# TurretController.net
KiCad netlist of a schematic drawn in EAGLE
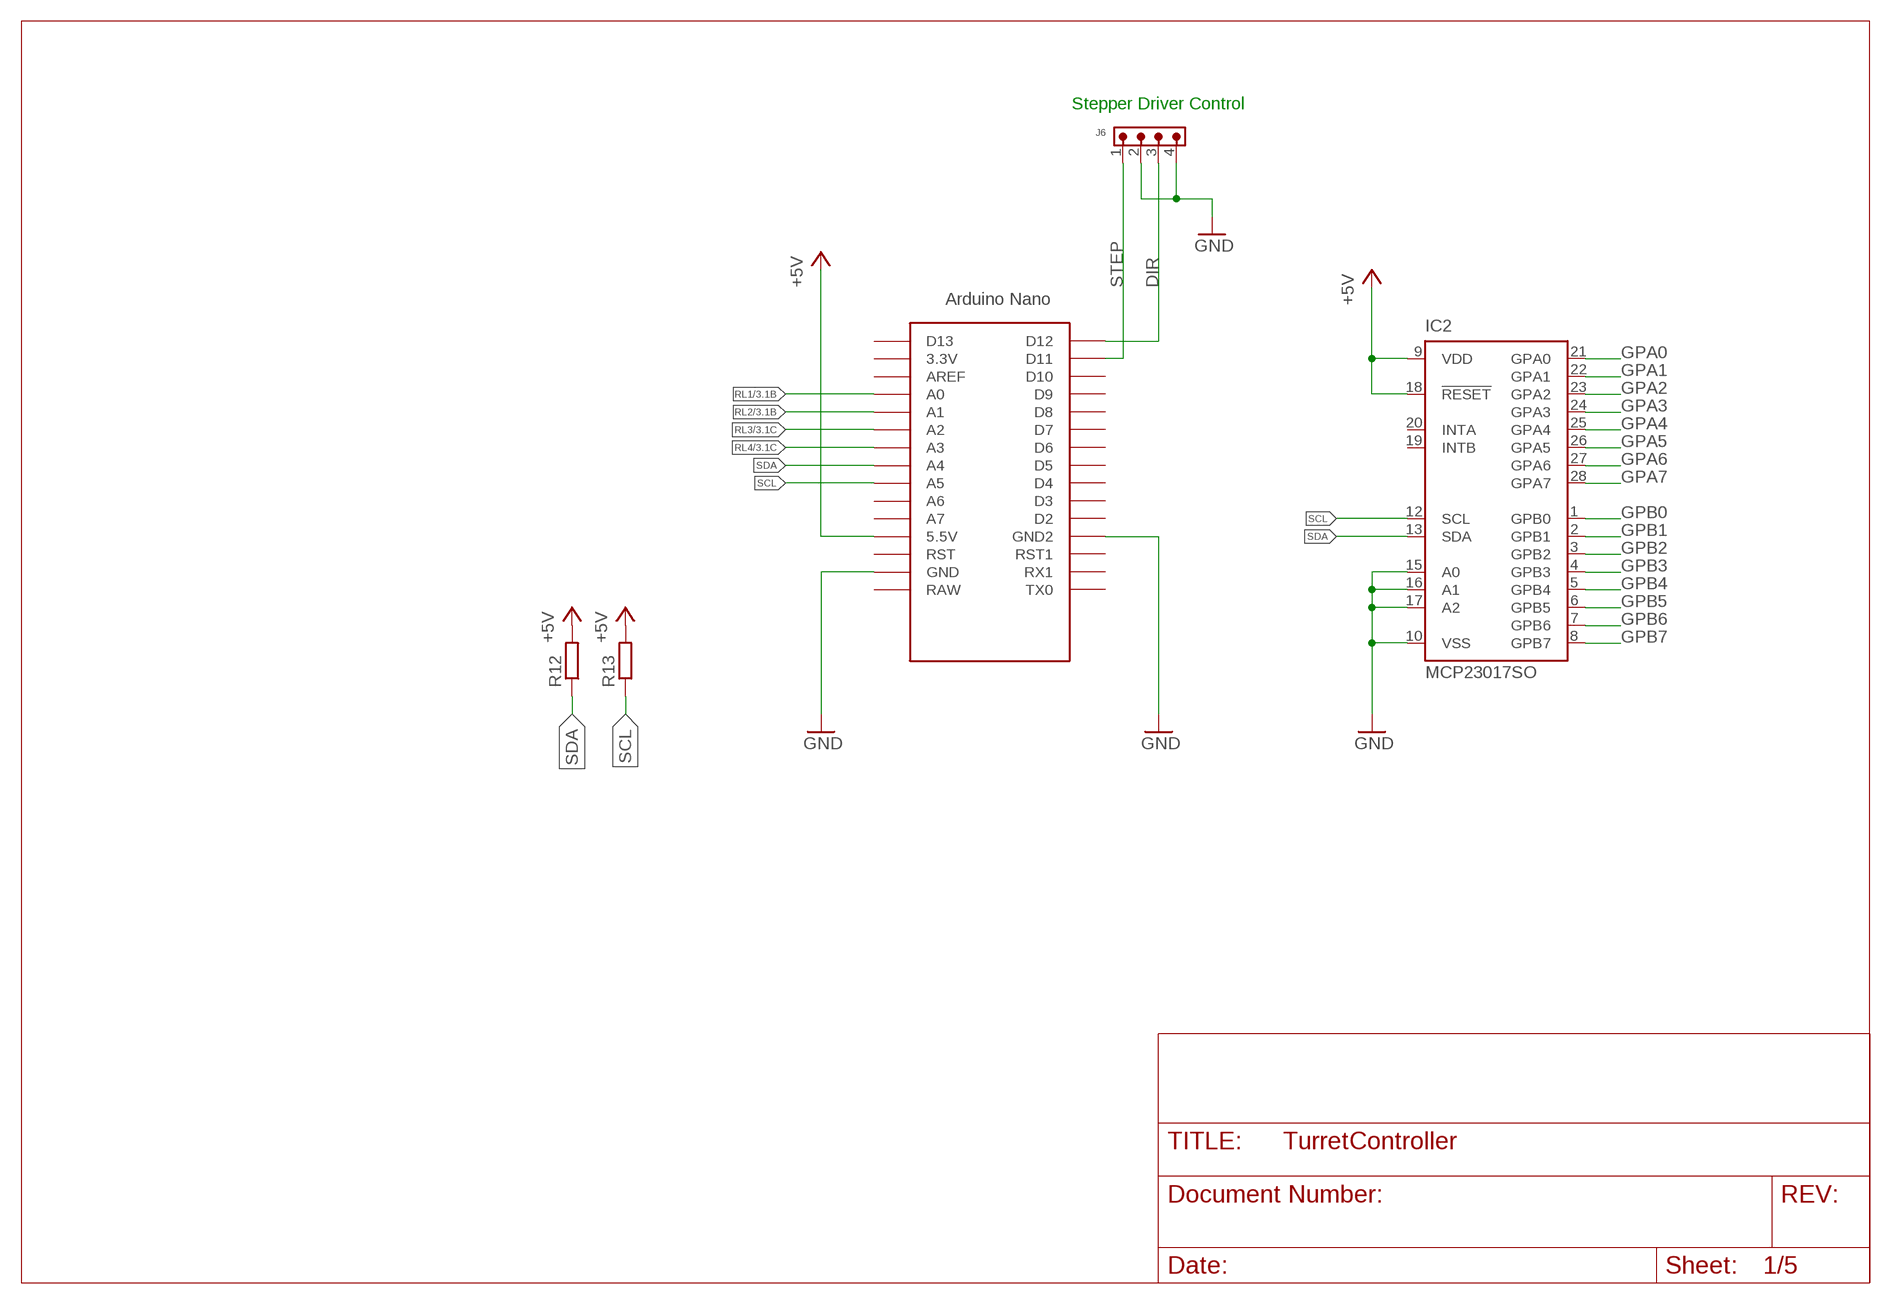
[diagram p0: schematic, sheet 1]
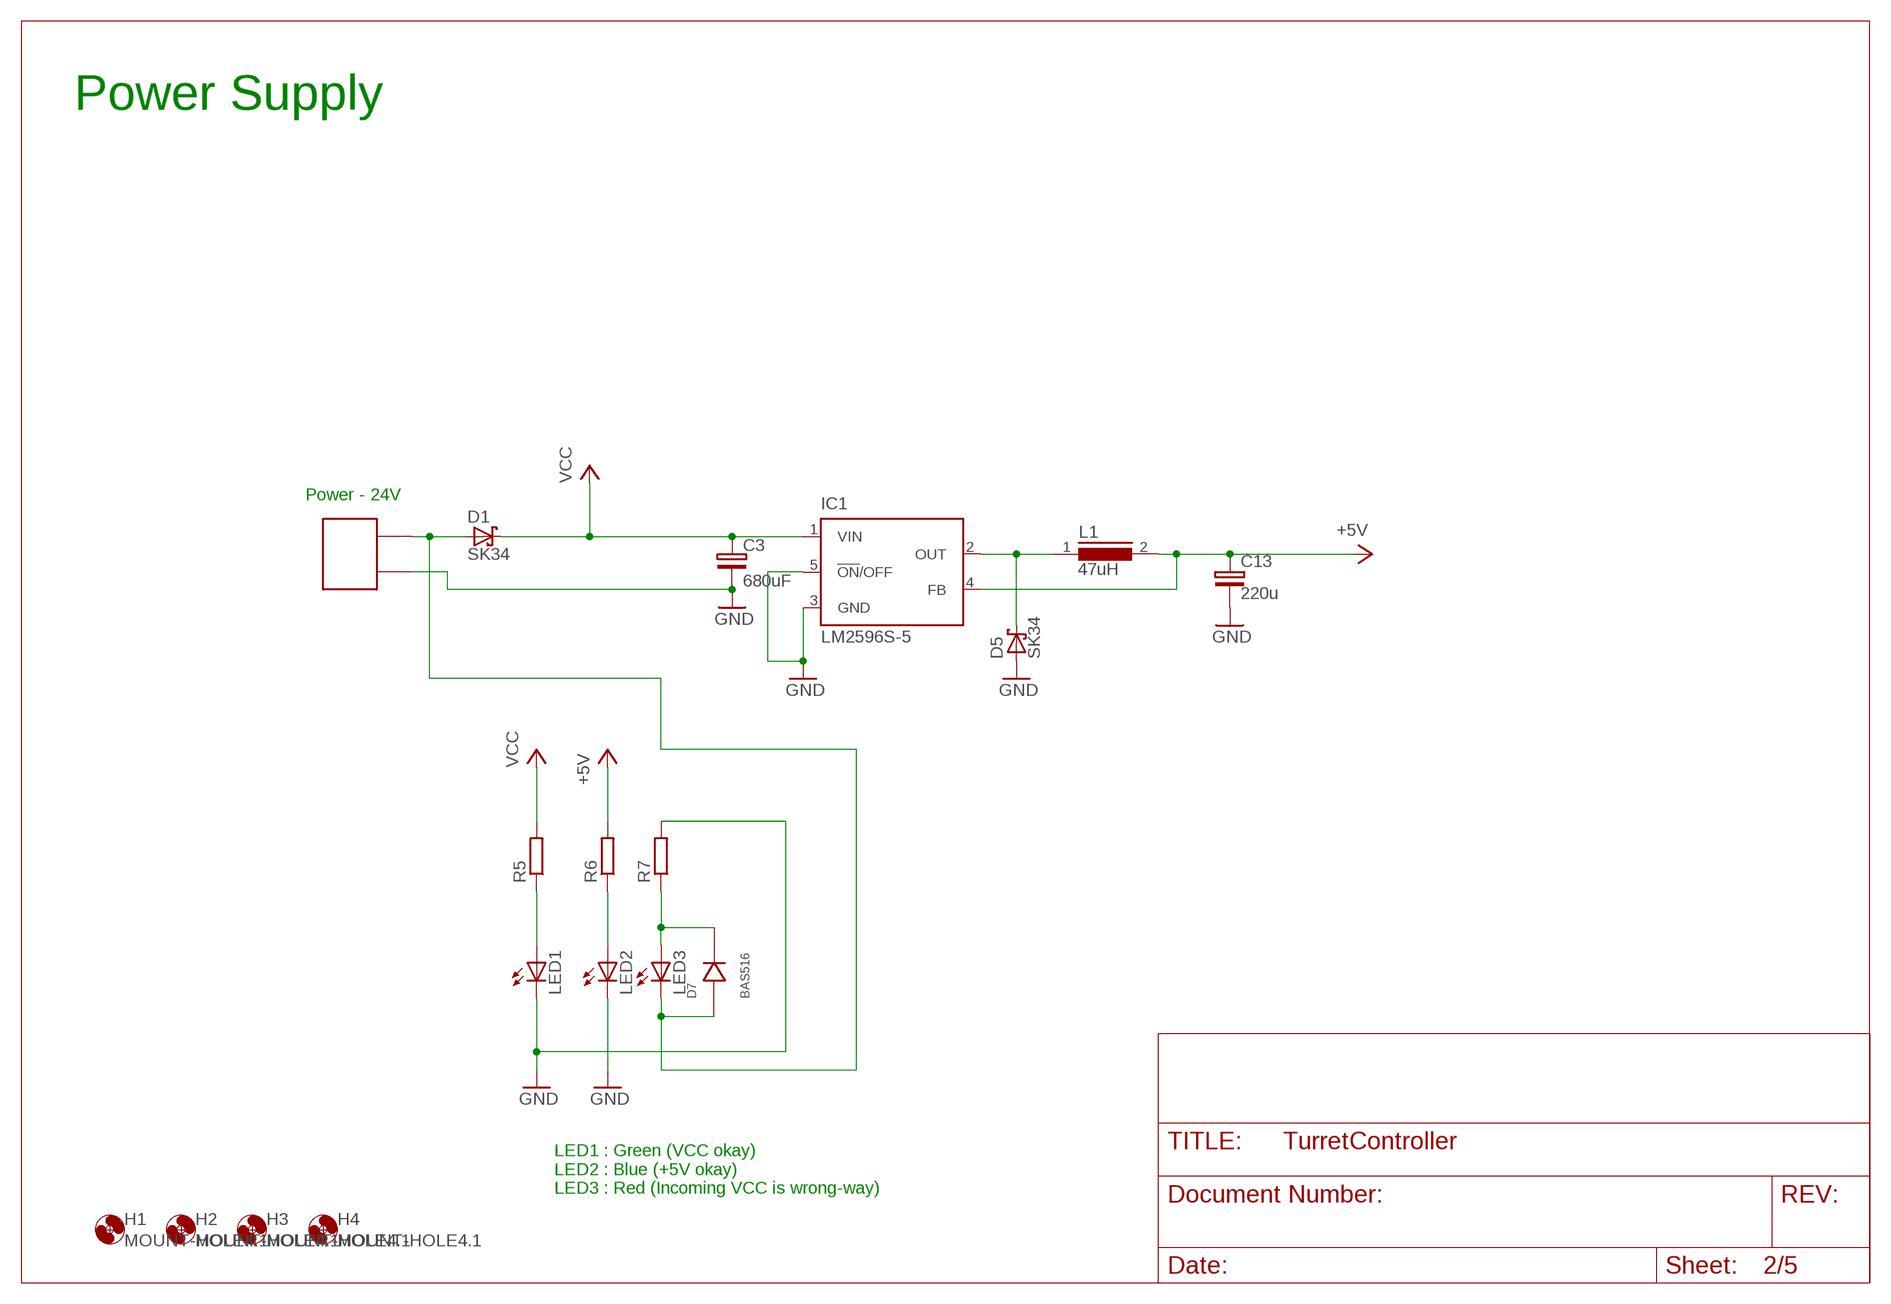
[diagram p1: schematic, sheet 2]
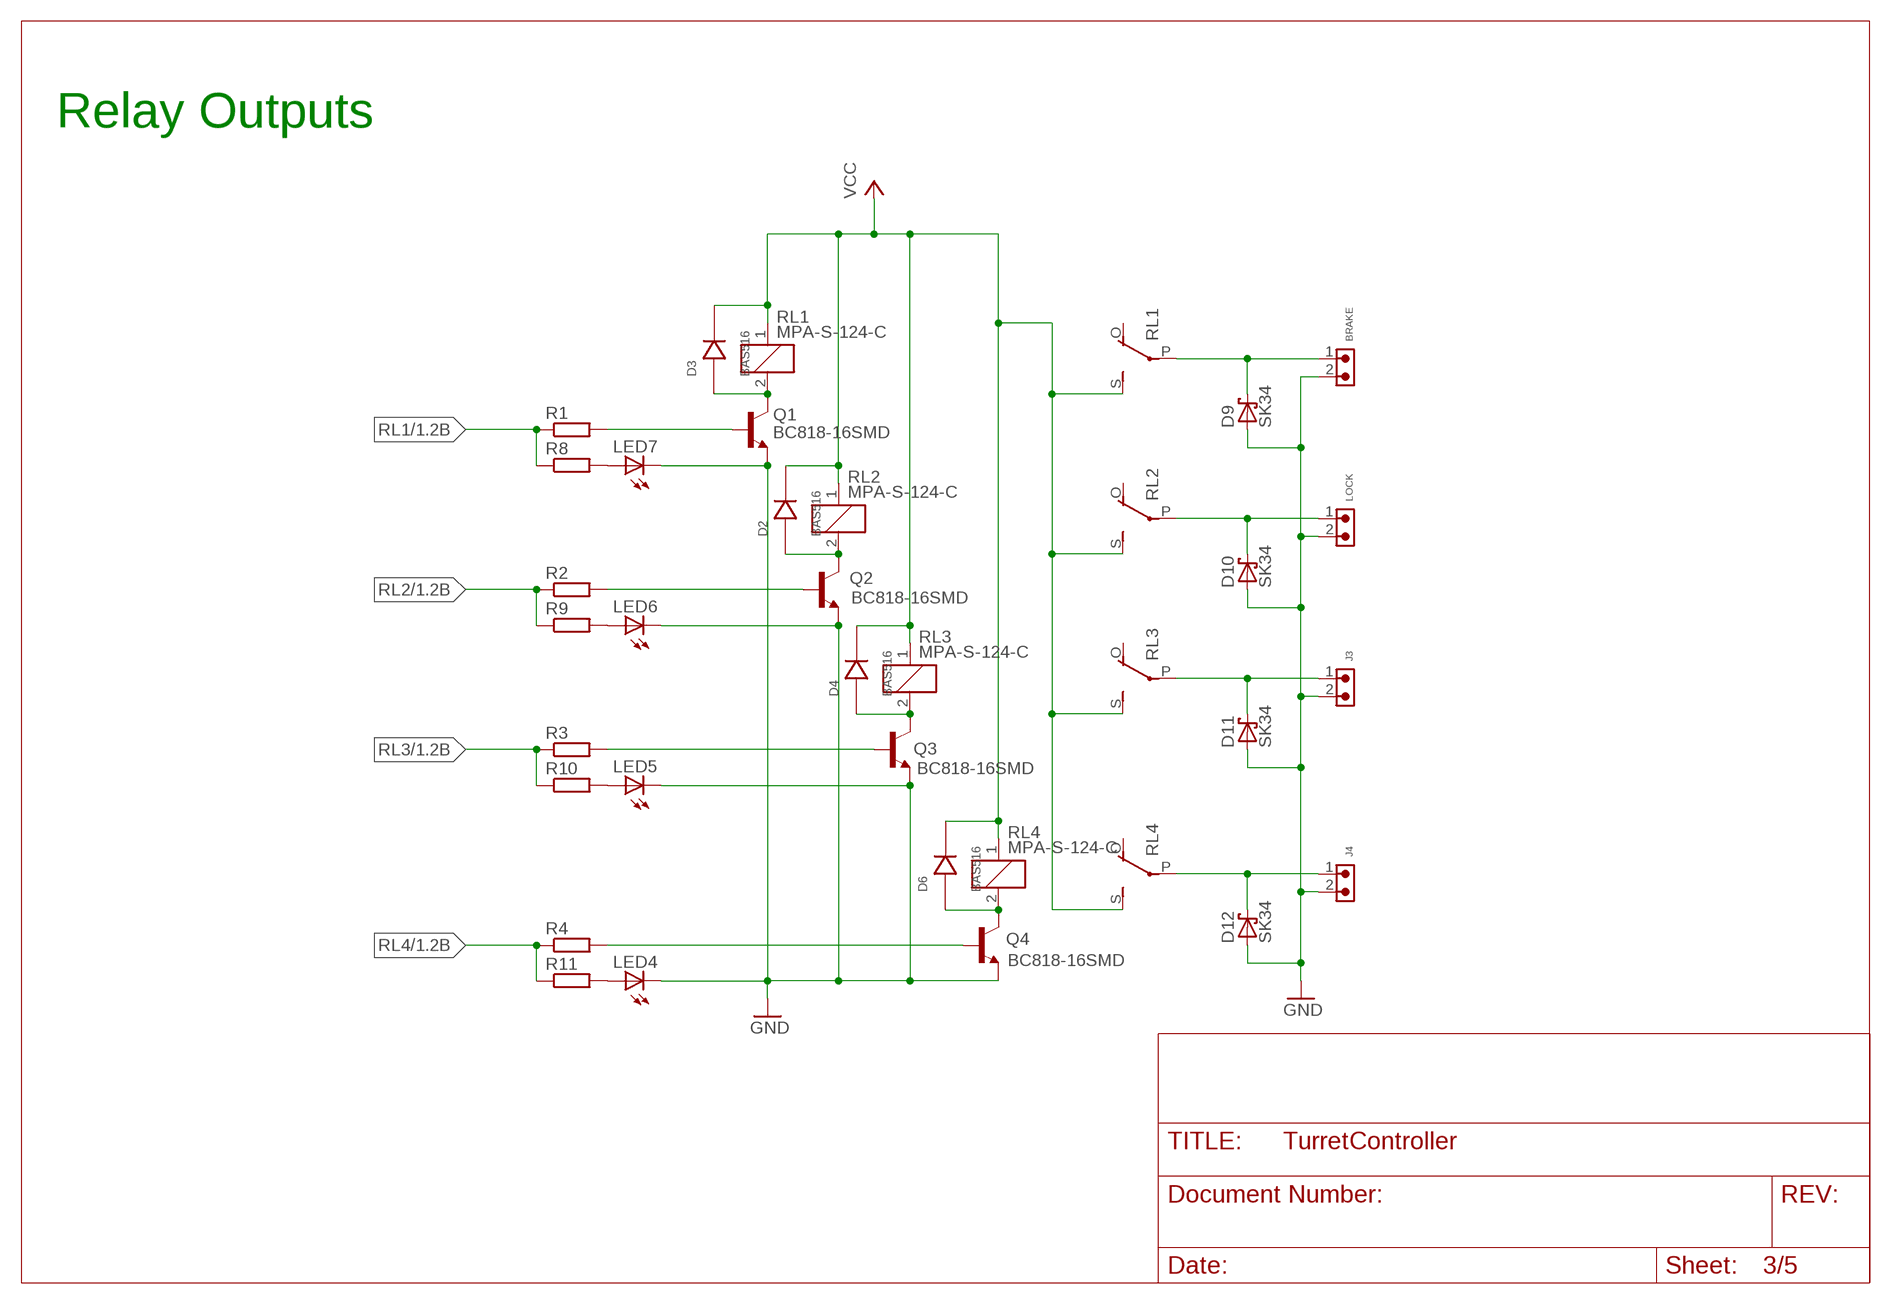
[diagram p2: schematic, sheet 3]
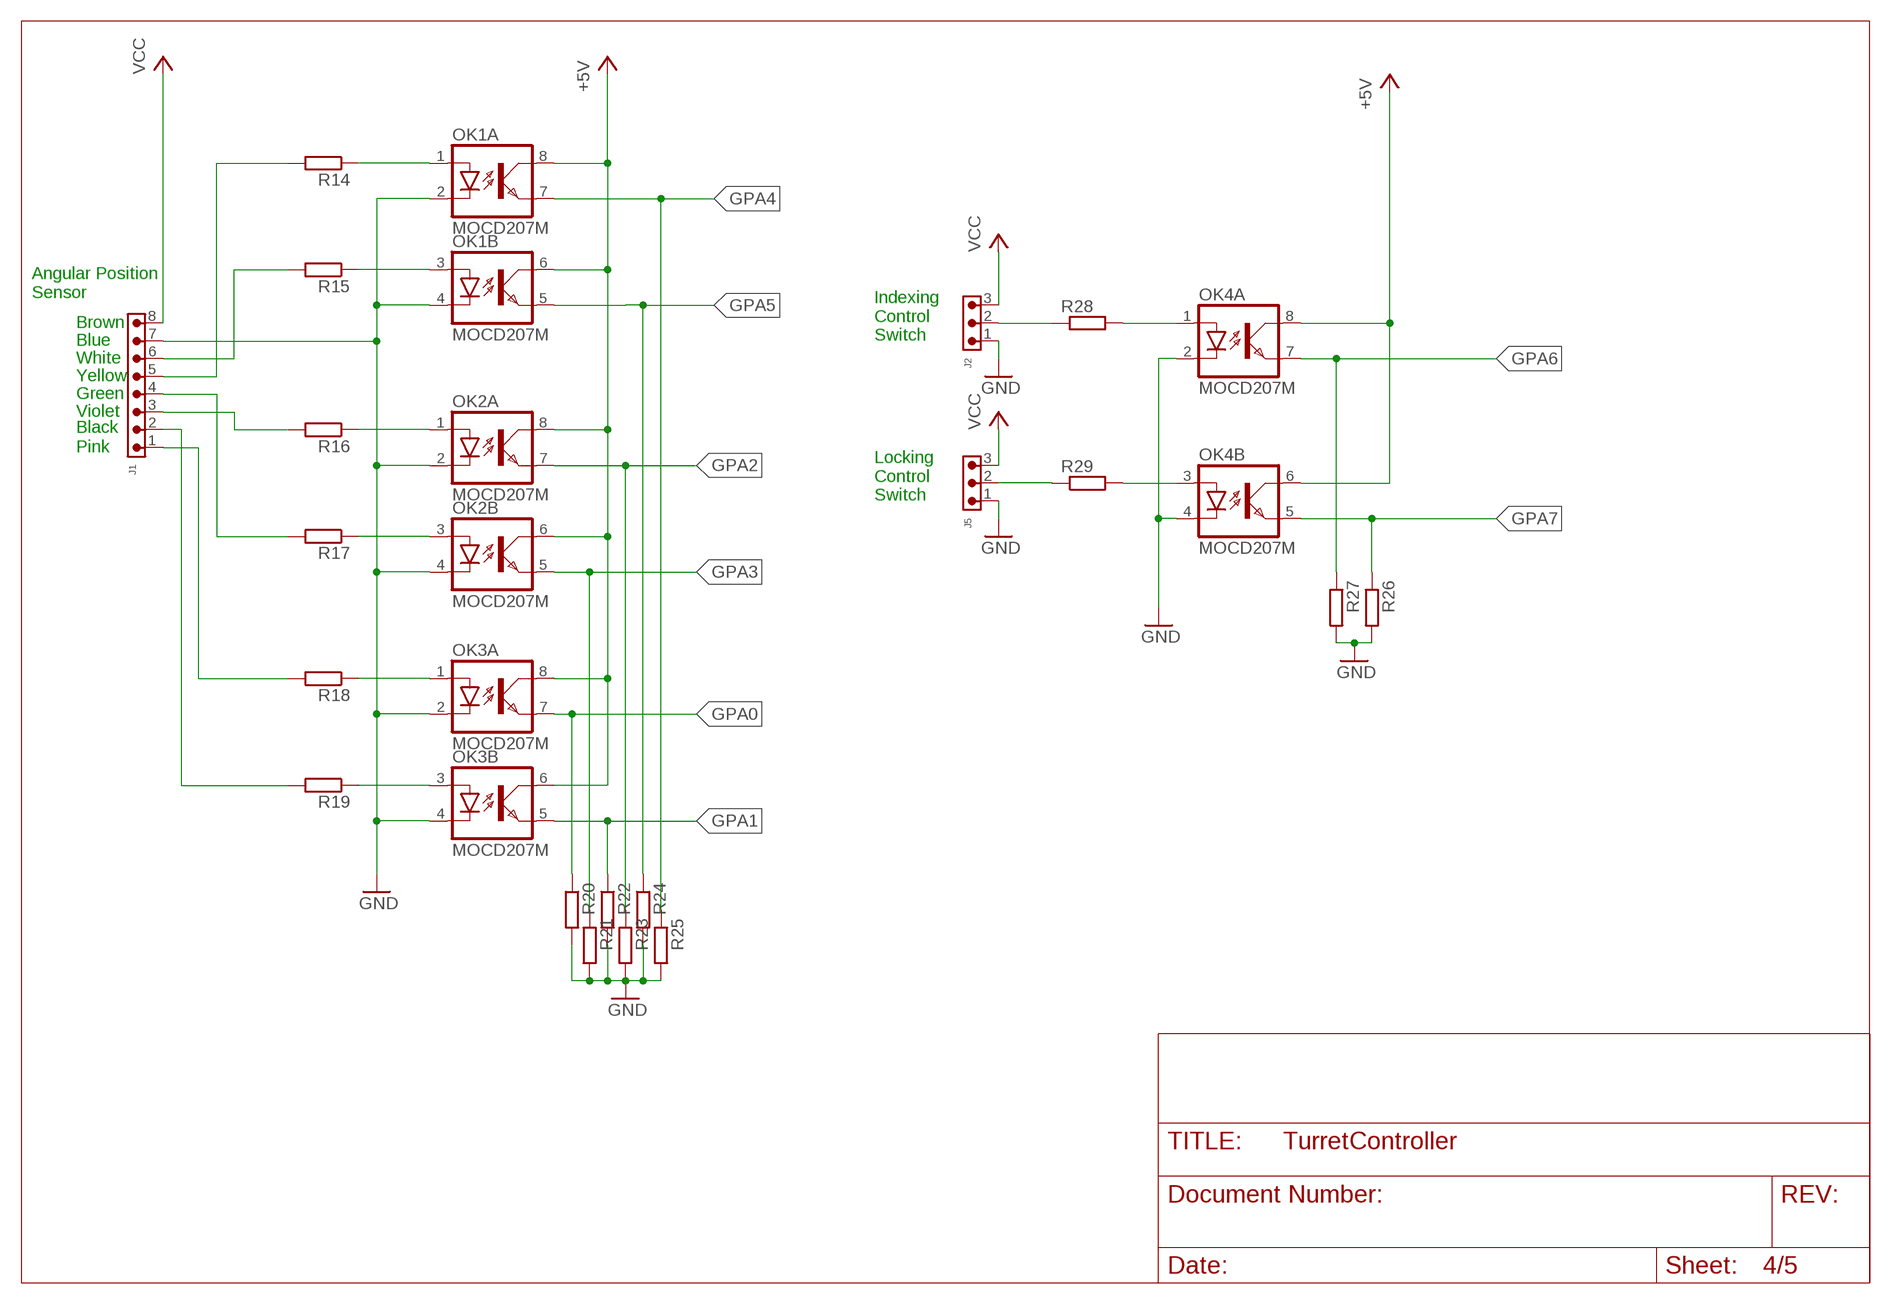
[diagram p3: schematic, sheet 4]
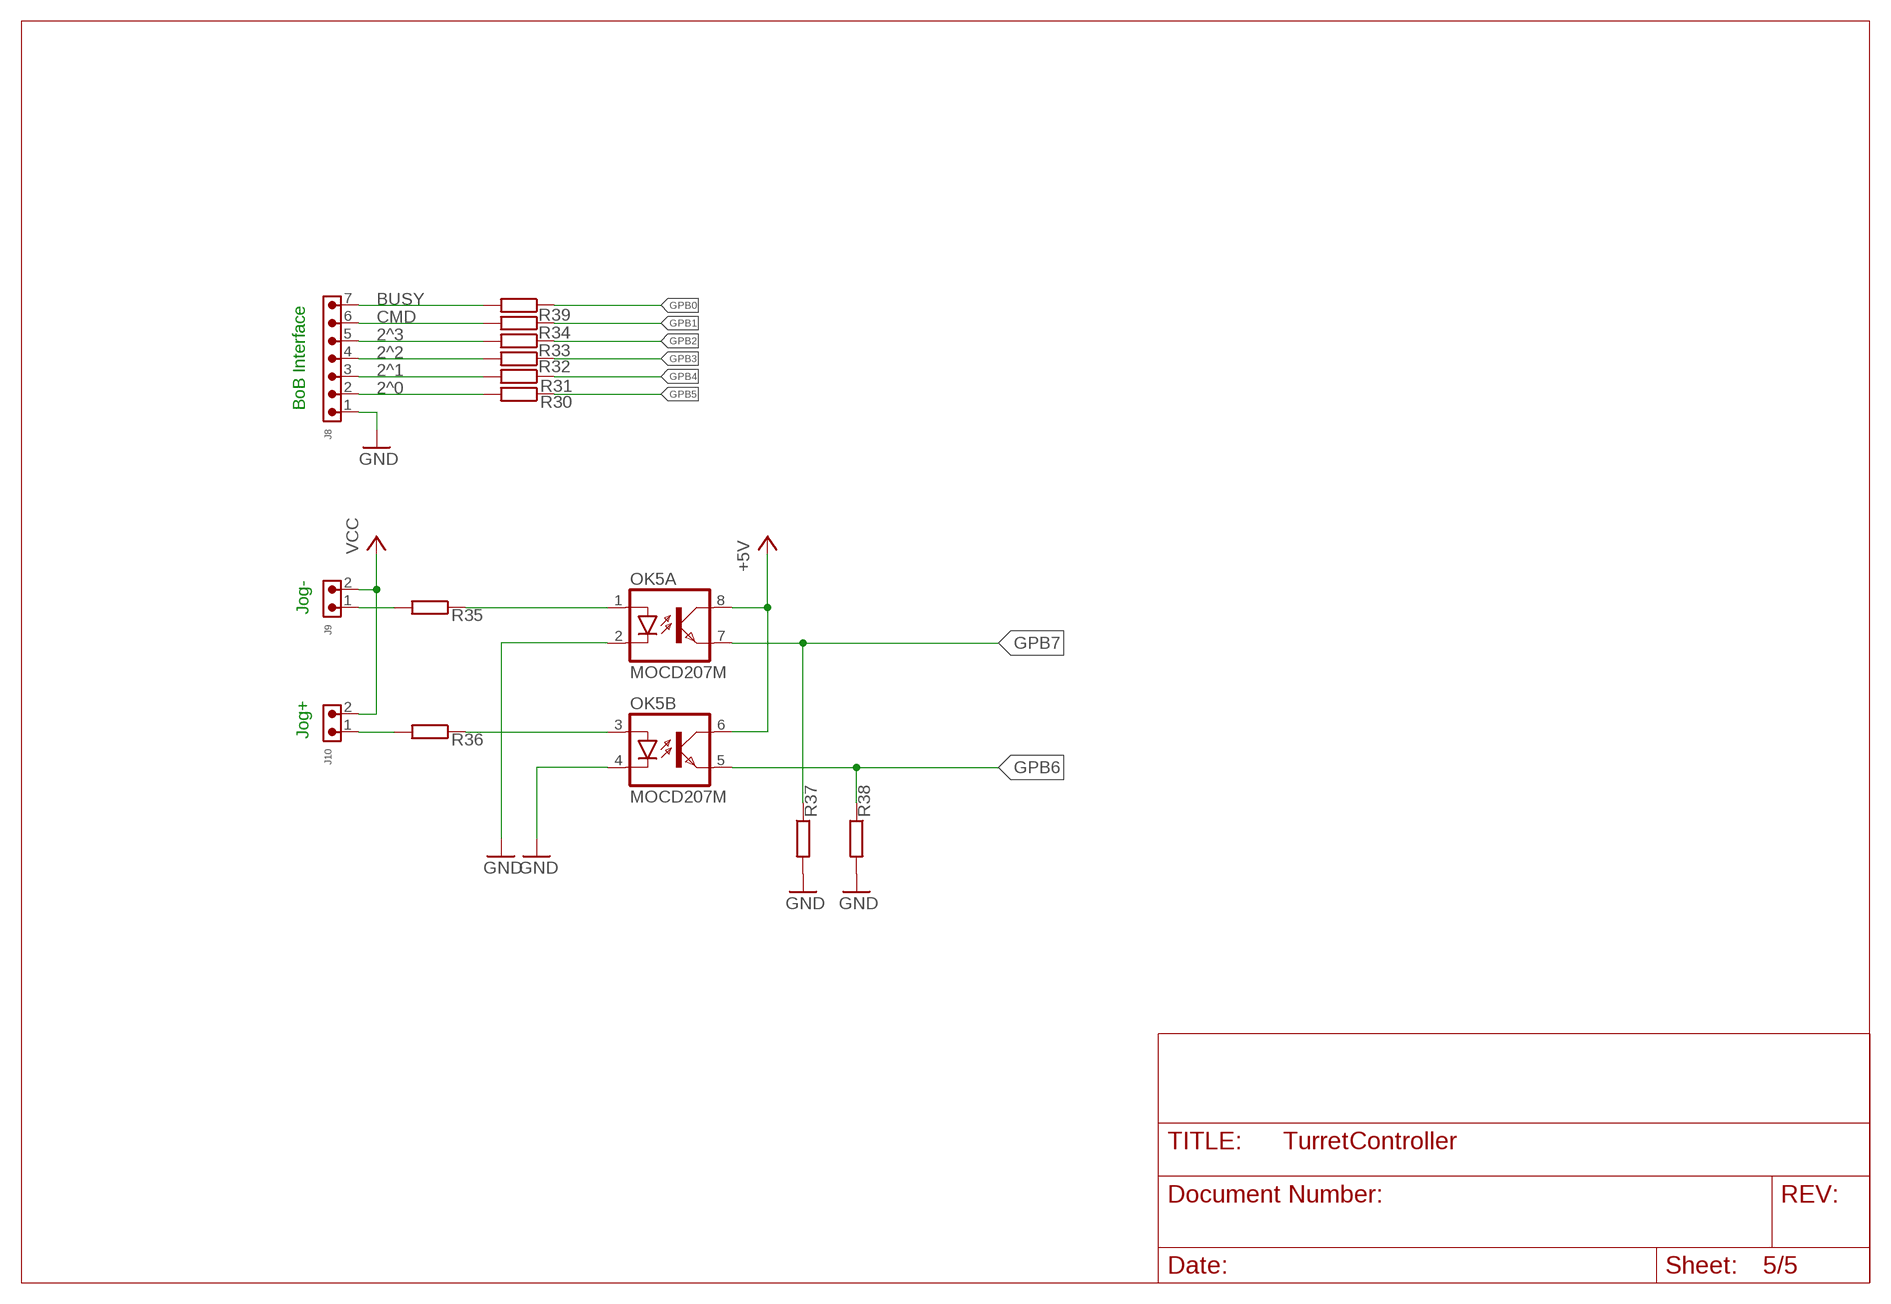
[diagram p4: schematic, sheet 5]

(export (version "E")
  (design (tool "Eeschema 10.0.6"))
  (components
    (comp (ref "BRAKE")
      (value "691305330002")
      (footprint "eagle-import:691305330002")
      (libsource (lib "eagle-import") (part "691305330002"))
    )
    (comp (ref "D2")
      (value "BAS516")
      (footprint "eagle-import:SOD523")
      (libsource (lib "eagle-import") (part "BAS516"))
    )
    (comp (ref "D3")
      (value "BAS516")
      (footprint "eagle-import:SOD523")
      (libsource (lib "eagle-import") (part "BAS516"))
    )
    (comp (ref "D4")
      (value "BAS516")
      (footprint "eagle-import:SOD523")
      (libsource (lib "eagle-import") (part "BAS516"))
    )
    (comp (ref "D6")
      (value "BAS516")
      (footprint "eagle-import:SOD523")
      (libsource (lib "eagle-import") (part "BAS516"))
    )
    (comp (ref "D9")
      (value "SK34")
      (footprint "eagle-import:DO214AC")
      (fields (field (name "SPICEPREFIX") "D"))
      (libsource (lib "eagle-import") (part "SK34"))
    )
    (comp (ref "D10")
      (value "SK34")
      (footprint "eagle-import:DO214AC")
      (fields (field (name "SPICEPREFIX") "D"))
      (libsource (lib "eagle-import") (part "SK34"))
    )
    (comp (ref "D11")
      (value "SK34")
      (footprint "eagle-import:DO214AC")
      (fields (field (name "SPICEPREFIX") "D"))
      (libsource (lib "eagle-import") (part "SK34"))
    )
    (comp (ref "D12")
      (value "SK34")
      (footprint "eagle-import:DO214AC")
      (fields (field (name "SPICEPREFIX") "D"))
      (libsource (lib "eagle-import") (part "SK34"))
    )
    (comp (ref "J3")
      (value "691305330002")
      (footprint "eagle-import:691305330002")
      (libsource (lib "eagle-import") (part "691305330002"))
    )
    (comp (ref "J4")
      (value "691305330002")
      (footprint "eagle-import:691305330002")
      (libsource (lib "eagle-import") (part "691305330002"))
    )
    (comp (ref "LED4")
      (value "LEDCHIPLED_0805")
      (footprint "eagle-import:CHIPLED_0805")
      (libsource (lib "eagle-import") (part "LEDCHIPLED_0805"))
    )
    (comp (ref "LED5")
      (value "LEDCHIPLED_0805")
      (footprint "eagle-import:CHIPLED_0805")
      (libsource (lib "eagle-import") (part "LEDCHIPLED_0805"))
    )
    (comp (ref "LED6")
      (value "LEDCHIPLED_0805")
      (footprint "eagle-import:CHIPLED_0805")
      (libsource (lib "eagle-import") (part "LEDCHIPLED_0805"))
    )
    (comp (ref "LED7")
      (value "LEDCHIPLED_0805")
      (footprint "eagle-import:CHIPLED_0805")
      (libsource (lib "eagle-import") (part "LEDCHIPLED_0805"))
    )
    (comp (ref "LOCK")
      (value "691305330002")
      (footprint "eagle-import:691305330002")
      (libsource (lib "eagle-import") (part "691305330002"))
    )
    (comp (ref "Q1")
      (value "BC818-16SMD")
      (footprint "eagle-import:SOT23-BEC")
      (libsource (lib "eagle-import") (part "BC818SMD-16"))
    )
    (comp (ref "Q2")
      (value "BC818-16SMD")
      (footprint "eagle-import:SOT23-BEC")
      (libsource (lib "eagle-import") (part "BC818SMD-16"))
    )
    (comp (ref "Q3")
      (value "BC818-16SMD")
      (footprint "eagle-import:SOT23-BEC")
      (libsource (lib "eagle-import") (part "BC818SMD-16"))
    )
    (comp (ref "Q4")
      (value "BC818-16SMD")
      (footprint "eagle-import:SOT23-BEC")
      (libsource (lib "eagle-import") (part "BC818SMD-16"))
    )
    (comp (ref "R1")
      (value "R-EU_R0805")
      (footprint "eagle-import:R0805")
      (libsource (lib "eagle-import") (part "R-EU_R0805"))
    )
    (comp (ref "R2")
      (value "R-EU_R0805")
      (footprint "eagle-import:R0805")
      (libsource (lib "eagle-import") (part "R-EU_R0805"))
    )
    (comp (ref "R3")
      (value "R-EU_R0805")
      (footprint "eagle-import:R0805")
      (libsource (lib "eagle-import") (part "R-EU_R0805"))
    )
    (comp (ref "R4")
      (value "R-EU_R0805")
      (footprint "eagle-import:R0805")
      (libsource (lib "eagle-import") (part "R-EU_R0805"))
    )
    (comp (ref "R8")
      (value "R-EU_R0805")
      (footprint "eagle-import:R0805")
      (libsource (lib "eagle-import") (part "R-EU_R0805"))
    )
    (comp (ref "R9")
      (value "R-EU_R0805")
      (footprint "eagle-import:R0805")
      (libsource (lib "eagle-import") (part "R-EU_R0805"))
    )
    (comp (ref "R10")
      (value "R-EU_R0805")
      (footprint "eagle-import:R0805")
      (libsource (lib "eagle-import") (part "R-EU_R0805"))
    )
    (comp (ref "R11")
      (value "R-EU_R0805")
      (footprint "eagle-import:R0805")
      (libsource (lib "eagle-import") (part "R-EU_R0805"))
    )
    (comp (ref "RL1")
      (value "MPA-S-124-C")
      (footprint "eagle-import:G5LE")
      (libsource (lib "eagle-import") (part "MPA-S-124-C"))
    )
    (comp (ref "RL2")
      (value "MPA-S-124-C")
      (footprint "eagle-import:G5LE")
      (libsource (lib "eagle-import") (part "MPA-S-124-C"))
    )
    (comp (ref "RL3")
      (value "MPA-S-124-C")
      (footprint "eagle-import:G5LE")
      (libsource (lib "eagle-import") (part "MPA-S-124-C"))
    )
    (comp (ref "RL4")
      (value "MPA-S-124-C")
      (footprint "eagle-import:G5LE")
      (libsource (lib "eagle-import") (part "MPA-S-124-C"))
    )
    (comp (ref "C3")
      (value "680uF")
      (footprint "eagle-import:C8.15X4X16.5")
      (fields (field (name "SPICEPREFIX") "C"))
      (libsource (lib "eagle-import") (part "C-EU-ELECT680UF/25V"))
    )
    (comp (ref "C13")
      (value "220u")
      (footprint "eagle-import:PAN-PTH-8X11X3.5")
      (fields (field (name "SPICEPREFIX") "C"))
      (libsource (lib "eagle-import") (part "PANASONIC-PTH220UF-25V"))
    )
    (comp (ref "CN1")
      (value "2EDG-2")
      (footprint "eagle-import:2EDG-2")
      (libsource (lib "eagle-import") (part "2EDG-2"))
    )
    (comp (ref "D1")
      (value "SK34")
      (footprint "eagle-import:DO214AC")
      (fields (field (name "SPICEPREFIX") "D"))
      (libsource (lib "eagle-import") (part "SK34"))
    )
    (comp (ref "D5")
      (value "SK34")
      (footprint "eagle-import:DO214AC")
      (fields (field (name "SPICEPREFIX") "D"))
      (libsource (lib "eagle-import") (part "SK34"))
    )
    (comp (ref "D7")
      (value "BAS516")
      (footprint "eagle-import:SOD523")
      (libsource (lib "eagle-import") (part "BAS516"))
    )
    (comp (ref "H1")
      (value "MOUNT-HOLE4.1")
      (footprint "eagle-import:4,1")
      (libsource (lib "eagle-import") (part "MOUNT-HOLE4.1"))
    )
    (comp (ref "H2")
      (value "MOUNT-HOLE4.1")
      (footprint "eagle-import:4,1")
      (libsource (lib "eagle-import") (part "MOUNT-HOLE4.1"))
    )
    (comp (ref "H3")
      (value "MOUNT-HOLE4.1")
      (footprint "eagle-import:4,1")
      (libsource (lib "eagle-import") (part "MOUNT-HOLE4.1"))
    )
    (comp (ref "H4")
      (value "MOUNT-HOLE4.1")
      (footprint "eagle-import:4,1")
      (libsource (lib "eagle-import") (part "MOUNT-HOLE4.1"))
    )
    (comp (ref "IC1")
      (value "LM2596S-5")
      (footprint "eagle-import:TO263-5")
      (fields
        (field (name "MF") "NATIONAL SEMICONDUCTOR")
        (field (name "MPN") "LM2596S-ADJ/NOPB")
        (field (name "SPICEPREFIX") "X")
      )
      (libsource (lib "eagle-import") (part "LM2596S"))
    )
    (comp (ref "L1")
      (value "47uH")
      (footprint "eagle-import:B82476A1")
      (fields (field (name "SPICEPREFIX") "L"))
      (libsource (lib "eagle-import") (part "INDUCTOR-SMD"))
    )
    (comp (ref "LED1")
      (value "LEDCHIPLED_0805")
      (footprint "eagle-import:CHIPLED_0805")
      (libsource (lib "eagle-import") (part "LEDCHIPLED_0805"))
    )
    (comp (ref "LED2")
      (value "LEDCHIPLED_0805")
      (footprint "eagle-import:CHIPLED_0805")
      (libsource (lib "eagle-import") (part "LEDCHIPLED_0805"))
    )
    (comp (ref "LED3")
      (value "LEDCHIPLED_0805")
      (footprint "eagle-import:CHIPLED_0805")
      (libsource (lib "eagle-import") (part "LEDCHIPLED_0805"))
    )
    (comp (ref "R5")
      (value "R-EU_R0805")
      (footprint "eagle-import:R0805")
      (libsource (lib "eagle-import") (part "R-EU_R0805"))
    )
    (comp (ref "R6")
      (value "R-EU_R0805")
      (footprint "eagle-import:R0805")
      (libsource (lib "eagle-import") (part "R-EU_R0805"))
    )
    (comp (ref "R7")
      (value "R-EU_R0805")
      (footprint "eagle-import:R0805")
      (libsource (lib "eagle-import") (part "R-EU_R0805"))
    )
    (comp (ref "IC2")
      (value "MCP23017SO")
      (footprint "eagle-import:SO28W")
      (fields (field (name "MF") "MICROCHIP") (field (name "MPN") "MCP23017-E/SO"))
      (libsource (lib "eagle-import") (part "MCP23017SO"))
    )
    (comp (ref "J6")
      (value "691305330004")
      (footprint "eagle-import:691305330004")
      (libsource (lib "eagle-import") (part "691305330004"))
    )
    (comp (ref "R12")
      (value "R-EU_R0805")
      (footprint "eagle-import:R0805")
      (libsource (lib "eagle-import") (part "R-EU_R0805"))
    )
    (comp (ref "R13")
      (value "R-EU_R0805")
      (footprint "eagle-import:R0805")
      (libsource (lib "eagle-import") (part "R-EU_R0805"))
    )
    (comp (ref "U$1")
      (value "NANO")
      (footprint "eagle-import:NANO")
      (libsource (lib "eagle-import") (part "NANO"))
    )
    (comp (ref "J1")
      (value "691305330008")
      (footprint "eagle-import:691305330008")
      (libsource (lib "eagle-import") (part "691305330008"))
    )
    (comp (ref "J2")
      (value "691305330003")
      (footprint "eagle-import:691305330003")
      (libsource (lib "eagle-import") (part "691305330003"))
    )
    (comp (ref "J5")
      (value "691305330003")
      (footprint "eagle-import:691305330003")
      (libsource (lib "eagle-import") (part "691305330003"))
    )
    (comp (ref "OK1")
      (value "MOCD207M")
      (footprint "eagle-import:SOIC08-FAIRCHILD")
      (fields (field (name "MF") "FAIRCHILD SEMICONDUCTOR") (field (name "MPN") "MOCD207-M"))
      (libsource (lib "eagle-import") (part "MOCD20M7"))
    )
    (comp (ref "OK2")
      (value "MOCD207M")
      (footprint "eagle-import:SOIC08-FAIRCHILD")
      (fields (field (name "MF") "FAIRCHILD SEMICONDUCTOR") (field (name "MPN") "MOCD207-M"))
      (libsource (lib "eagle-import") (part "MOCD20M7"))
    )
    (comp (ref "OK3")
      (value "MOCD207M")
      (footprint "eagle-import:SOIC08-FAIRCHILD")
      (fields (field (name "MF") "FAIRCHILD SEMICONDUCTOR") (field (name "MPN") "MOCD207-M"))
      (libsource (lib "eagle-import") (part "MOCD20M7"))
    )
    (comp (ref "OK4")
      (value "MOCD207M")
      (footprint "eagle-import:SOIC08-FAIRCHILD")
      (fields (field (name "MF") "FAIRCHILD SEMICONDUCTOR") (field (name "MPN") "MOCD207-M"))
      (libsource (lib "eagle-import") (part "MOCD20M7"))
    )
    (comp (ref "R14")
      (value "R-EU_R0805")
      (footprint "eagle-import:R0805")
      (libsource (lib "eagle-import") (part "R-EU_R0805"))
    )
    (comp (ref "R15")
      (value "R-EU_R0805")
      (footprint "eagle-import:R0805")
      (libsource (lib "eagle-import") (part "R-EU_R0805"))
    )
    (comp (ref "R16")
      (value "R-EU_R0805")
      (footprint "eagle-import:R0805")
      (libsource (lib "eagle-import") (part "R-EU_R0805"))
    )
    (comp (ref "R17")
      (value "R-EU_R0805")
      (footprint "eagle-import:R0805")
      (libsource (lib "eagle-import") (part "R-EU_R0805"))
    )
    (comp (ref "R18")
      (value "R-EU_R0805")
      (footprint "eagle-import:R0805")
      (libsource (lib "eagle-import") (part "R-EU_R0805"))
    )
    (comp (ref "R19")
      (value "R-EU_R0805")
      (footprint "eagle-import:R0805")
      (libsource (lib "eagle-import") (part "R-EU_R0805"))
    )
    (comp (ref "R20")
      (value "R-EU_R0805")
      (footprint "eagle-import:R0805")
      (libsource (lib "eagle-import") (part "R-EU_R0805"))
    )
    (comp (ref "R21")
      (value "R-EU_R0805")
      (footprint "eagle-import:R0805")
      (libsource (lib "eagle-import") (part "R-EU_R0805"))
    )
    (comp (ref "R22")
      (value "R-EU_R0805")
      (footprint "eagle-import:R0805")
      (libsource (lib "eagle-import") (part "R-EU_R0805"))
    )
    (comp (ref "R23")
      (value "R-EU_R0805")
      (footprint "eagle-import:R0805")
      (libsource (lib "eagle-import") (part "R-EU_R0805"))
    )
    (comp (ref "R24")
      (value "R-EU_R0805")
      (footprint "eagle-import:R0805")
      (libsource (lib "eagle-import") (part "R-EU_R0805"))
    )
    (comp (ref "R25")
      (value "R-EU_R0805")
      (footprint "eagle-import:R0805")
      (libsource (lib "eagle-import") (part "R-EU_R0805"))
    )
    (comp (ref "R26")
      (value "R-EU_R0805")
      (footprint "eagle-import:R0805")
      (libsource (lib "eagle-import") (part "R-EU_R0805"))
    )
    (comp (ref "R27")
      (value "R-EU_R0805")
      (footprint "eagle-import:R0805")
      (libsource (lib "eagle-import") (part "R-EU_R0805"))
    )
    (comp (ref "R28")
      (value "R-EU_R0805")
      (footprint "eagle-import:R0805")
      (libsource (lib "eagle-import") (part "R-EU_R0805"))
    )
    (comp (ref "R29")
      (value "R-EU_R0805")
      (footprint "eagle-import:R0805")
      (libsource (lib "eagle-import") (part "R-EU_R0805"))
    )
    (comp (ref "J8")
      (value "691305330007")
      (footprint "eagle-import:691305330007")
      (libsource (lib "eagle-import") (part "691305330007"))
    )
    (comp (ref "J9")
      (value "691305330002")
      (footprint "eagle-import:691305330002")
      (libsource (lib "eagle-import") (part "691305330002"))
    )
    (comp (ref "J10")
      (value "691305330002")
      (footprint "eagle-import:691305330002")
      (libsource (lib "eagle-import") (part "691305330002"))
    )
    (comp (ref "OK5")
      (value "MOCD207M")
      (footprint "eagle-import:SOIC08-FAIRCHILD")
      (fields (field (name "MF") "FAIRCHILD SEMICONDUCTOR") (field (name "MPN") "MOCD207-M"))
      (libsource (lib "eagle-import") (part "MOCD20M7"))
    )
    (comp (ref "R30")
      (value "R-EU_R0805")
      (footprint "eagle-import:R0805")
      (libsource (lib "eagle-import") (part "R-EU_R0805"))
    )
    (comp (ref "R31")
      (value "R-EU_R0805")
      (footprint "eagle-import:R0805")
      (libsource (lib "eagle-import") (part "R-EU_R0805"))
    )
    (comp (ref "R32")
      (value "R-EU_R0805")
      (footprint "eagle-import:R0805")
      (libsource (lib "eagle-import") (part "R-EU_R0805"))
    )
    (comp (ref "R33")
      (value "R-EU_R0805")
      (footprint "eagle-import:R0805")
      (libsource (lib "eagle-import") (part "R-EU_R0805"))
    )
    (comp (ref "R34")
      (value "R-EU_R0805")
      (footprint "eagle-import:R0805")
      (libsource (lib "eagle-import") (part "R-EU_R0805"))
    )
    (comp (ref "R35")
      (value "R-EU_R0805")
      (footprint "eagle-import:R0805")
      (libsource (lib "eagle-import") (part "R-EU_R0805"))
    )
    (comp (ref "R36")
      (value "R-EU_R0805")
      (footprint "eagle-import:R0805")
      (libsource (lib "eagle-import") (part "R-EU_R0805"))
    )
    (comp (ref "R37")
      (value "R-EU_R0805")
      (footprint "eagle-import:R0805")
      (libsource (lib "eagle-import") (part "R-EU_R0805"))
    )
    (comp (ref "R38")
      (value "R-EU_R0805")
      (footprint "eagle-import:R0805")
      (libsource (lib "eagle-import") (part "R-EU_R0805"))
    )
    (comp (ref "R39")
      (value "R-EU_R0805")
      (footprint "eagle-import:R0805")
      (libsource (lib "eagle-import") (part "R-EU_R0805"))
    )
  )
  (nets
    (net (code "1") (name "+5V") (class "Default")
      (node (ref "C13") (pin "+") (pinfunction "+_+") (pintype "passive"))
      (node (ref "IC1") (pin "4") (pinfunction "FB_4") (pintype "input"))
      (node (ref "IC2") (pin "18") (pinfunction "~{RESET}_18") (pintype "input"))
      (node (ref "IC2") (pin "9") (pinfunction "VDD_9") (pintype "power_in"))
      (node (ref "L1") (pin "2") (pinfunction "2_2") (pintype "passive"))
      (node (ref "OK1") (pin "6") (pinfunction "COL_6") (pintype "passive"))
      (node (ref "OK1") (pin "8") (pinfunction "COL_8") (pintype "passive"))
      (node (ref "OK2") (pin "6") (pinfunction "COL_6") (pintype "passive"))
      (node (ref "OK2") (pin "8") (pinfunction "COL_8") (pintype "passive"))
      (node (ref "OK3") (pin "6") (pinfunction "COL_6") (pintype "passive"))
      (node (ref "OK3") (pin "8") (pinfunction "COL_8") (pintype "passive"))
      (node (ref "OK4") (pin "6") (pinfunction "COL_6") (pintype "passive"))
      (node (ref "OK4") (pin "8") (pinfunction "COL_8") (pintype "passive"))
      (node (ref "OK5") (pin "6") (pinfunction "COL_6") (pintype "passive"))
      (node (ref "OK5") (pin "8") (pinfunction "COL_8") (pintype "passive"))
      (node (ref "R12") (pin "2") (pinfunction "2_2") (pintype "passive"))
      (node (ref "R13") (pin "2") (pinfunction "2_2") (pintype "passive"))
      (node (ref "R6") (pin "2") (pinfunction "2_2") (pintype "passive"))
      (node (ref "U$1") (pin "5V") (pinfunction "5.5V_5V") (pintype "bidirectional"))
    )
    (net (code "2") (name "2^0") (class "Default")
      (node (ref "J8") (pin "2") (pinfunction "2_2") (pintype "passive"))
      (node (ref "R30") (pin "2") (pinfunction "2_2") (pintype "passive"))
    )
    (net (code "3") (name "2^1") (class "Default")
      (node (ref "J8") (pin "3") (pinfunction "3_3") (pintype "passive"))
      (node (ref "R31") (pin "2") (pinfunction "2_2") (pintype "passive"))
    )
    (net (code "4") (name "2^2") (class "Default")
      (node (ref "J8") (pin "4") (pinfunction "4_4") (pintype "passive"))
      (node (ref "R32") (pin "2") (pinfunction "2_2") (pintype "passive"))
    )
    (net (code "5") (name "2^3") (class "Default")
      (node (ref "J8") (pin "5") (pinfunction "5_5") (pintype "passive"))
      (node (ref "R33") (pin "2") (pinfunction "2_2") (pintype "passive"))
    )
    (net (code "6") (name "BUSY") (class "Default")
      (node (ref "J8") (pin "7") (pinfunction "7_7") (pintype "passive"))
      (node (ref "R39") (pin "2") (pinfunction "2_2") (pintype "passive"))
    )
    (net (code "7") (name "CMD") (class "Default")
      (node (ref "J8") (pin "6") (pinfunction "6_6") (pintype "passive"))
      (node (ref "R34") (pin "2") (pinfunction "2_2") (pintype "passive"))
    )
    (net (code "8") (name "DIR") (class "Default")
      (node (ref "J6") (pin "3") (pinfunction "3_3") (pintype "passive"))
      (node (ref "U$1") (pin "D12") (pinfunction "D12_D12") (pintype "bidirectional"))
    )
    (net (code "9") (name "GND") (class "Default")
      (node (ref "BRAKE") (pin "2") (pinfunction "2_2") (pintype "passive"))
      (node (ref "C13") (pin "-") (pinfunction "-_-") (pintype "passive"))
      (node (ref "C3") (pin "-") (pinfunction "-_-") (pintype "passive"))
      (node (ref "CN1") (pin "P$1") (pinfunction "P$1_P$1") (pintype "bidirectional"))
      (node (ref "D10") (pin "A") (pinfunction "A_A") (pintype "passive"))
      (node (ref "D11") (pin "A") (pinfunction "A_A") (pintype "passive"))
      (node (ref "D12") (pin "A") (pinfunction "A_A") (pintype "passive"))
      (node (ref "D5") (pin "A") (pinfunction "A_A") (pintype "passive"))
      (node (ref "D9") (pin "A") (pinfunction "A_A") (pintype "passive"))
      (node (ref "IC1") (pin "3") (pinfunction "GND_3") (pintype "power_in"))
      (node (ref "IC1") (pin "5") (pinfunction "~{ON}/OFF_5") (pintype "input"))
      (node (ref "IC2") (pin "10") (pinfunction "VSS_10") (pintype "power_in"))
      (node (ref "IC2") (pin "15") (pinfunction "A0_15") (pintype "input"))
      (node (ref "IC2") (pin "16") (pinfunction "A1_16") (pintype "input"))
      (node (ref "IC2") (pin "17") (pinfunction "A2_17") (pintype "input"))
      (node (ref "J1") (pin "7") (pinfunction "7_7") (pintype "passive"))
      (node (ref "J2") (pin "1") (pinfunction "1_1") (pintype "passive"))
      (node (ref "J3") (pin "2") (pinfunction "2_2") (pintype "passive"))
      (node (ref "J4") (pin "2") (pinfunction "2_2") (pintype "passive"))
      (node (ref "J5") (pin "1") (pinfunction "1_1") (pintype "passive"))
      (node (ref "J6") (pin "2") (pinfunction "2_2") (pintype "passive"))
      (node (ref "J6") (pin "4") (pinfunction "4_4") (pintype "passive"))
      (node (ref "J8") (pin "1") (pinfunction "1_1") (pintype "passive"))
      (node (ref "LED1") (pin "C") (pinfunction "C_C") (pintype "passive"))
      (node (ref "LED2") (pin "C") (pinfunction "C_C") (pintype "passive"))
      (node (ref "LED4") (pin "C") (pinfunction "C_C") (pintype "passive"))
      (node (ref "LED5") (pin "C") (pinfunction "C_C") (pintype "passive"))
      (node (ref "LED6") (pin "C") (pinfunction "C_C") (pintype "passive"))
      (node (ref "LED7") (pin "C") (pinfunction "C_C") (pintype "passive"))
      (node (ref "LOCK") (pin "2") (pinfunction "2_2") (pintype "passive"))
      (node (ref "OK1") (pin "2") (pinfunction "C_2") (pintype "passive"))
      (node (ref "OK1") (pin "4") (pinfunction "C_4") (pintype "passive"))
      (node (ref "OK2") (pin "2") (pinfunction "C_2") (pintype "passive"))
      (node (ref "OK2") (pin "4") (pinfunction "C_4") (pintype "passive"))
      (node (ref "OK3") (pin "2") (pinfunction "C_2") (pintype "passive"))
      (node (ref "OK3") (pin "4") (pinfunction "C_4") (pintype "passive"))
      (node (ref "OK4") (pin "2") (pinfunction "C_2") (pintype "passive"))
      (node (ref "OK4") (pin "4") (pinfunction "C_4") (pintype "passive"))
      (node (ref "OK5") (pin "2") (pinfunction "C_2") (pintype "passive"))
      (node (ref "OK5") (pin "4") (pinfunction "C_4") (pintype "passive"))
      (node (ref "Q1") (pin "E") (pinfunction "E_E") (pintype "passive"))
      (node (ref "Q2") (pin "E") (pinfunction "E_E") (pintype "passive"))
      (node (ref "Q3") (pin "E") (pinfunction "E_E") (pintype "passive"))
      (node (ref "Q4") (pin "E") (pinfunction "E_E") (pintype "passive"))
      (node (ref "R20") (pin "2") (pinfunction "2_2") (pintype "passive"))
      (node (ref "R21") (pin "2") (pinfunction "2_2") (pintype "passive"))
      (node (ref "R22") (pin "2") (pinfunction "2_2") (pintype "passive"))
      (node (ref "R23") (pin "2") (pinfunction "2_2") (pintype "passive"))
      (node (ref "R24") (pin "2") (pinfunction "2_2") (pintype "passive"))
      (node (ref "R25") (pin "2") (pinfunction "2_2") (pintype "passive"))
      (node (ref "R26") (pin "2") (pinfunction "2_2") (pintype "passive"))
      (node (ref "R27") (pin "2") (pinfunction "2_2") (pintype "passive"))
      (node (ref "R37") (pin "2") (pinfunction "2_2") (pintype "passive"))
      (node (ref "R38") (pin "2") (pinfunction "2_2") (pintype "passive"))
      (node (ref "R7") (pin "2") (pinfunction "2_2") (pintype "passive"))
      (node (ref "U$1") (pin "GND") (pinfunction "GND_GND") (pintype "bidirectional"))
      (node (ref "U$1") (pin "GND1") (pinfunction "GND2_GND1") (pintype "bidirectional"))
    )
    (net (code "10") (name "GPA0") (class "Default")
      (node (ref "IC2") (pin "21") (pinfunction "GPA0_21") (pintype "bidirectional"))
      (node (ref "OK3") (pin "7") (pinfunction "EMIT_7") (pintype "passive"))
      (node (ref "R20") (pin "1") (pinfunction "1_1") (pintype "passive"))
    )
    (net (code "11") (name "GPA1") (class "Default")
      (node (ref "IC2") (pin "22") (pinfunction "GPA1_22") (pintype "bidirectional"))
      (node (ref "OK3") (pin "5") (pinfunction "EMIT_5") (pintype "passive"))
      (node (ref "R22") (pin "1") (pinfunction "1_1") (pintype "passive"))
    )
    (net (code "12") (name "GPA2") (class "Default")
      (node (ref "IC2") (pin "23") (pinfunction "GPA2_23") (pintype "bidirectional"))
      (node (ref "OK2") (pin "7") (pinfunction "EMIT_7") (pintype "passive"))
      (node (ref "R23") (pin "1") (pinfunction "1_1") (pintype "passive"))
    )
    (net (code "13") (name "GPA3") (class "Default")
      (node (ref "IC2") (pin "24") (pinfunction "GPA3_24") (pintype "bidirectional"))
      (node (ref "OK2") (pin "5") (pinfunction "EMIT_5") (pintype "passive"))
      (node (ref "R21") (pin "1") (pinfunction "1_1") (pintype "passive"))
    )
    (net (code "14") (name "GPA4") (class "Default")
      (node (ref "IC2") (pin "25") (pinfunction "GPA4_25") (pintype "bidirectional"))
      (node (ref "OK1") (pin "7") (pinfunction "EMIT_7") (pintype "passive"))
      (node (ref "R25") (pin "1") (pinfunction "1_1") (pintype "passive"))
    )
    (net (code "15") (name "GPA5") (class "Default")
      (node (ref "IC2") (pin "26") (pinfunction "GPA5_26") (pintype "bidirectional"))
      (node (ref "OK1") (pin "5") (pinfunction "EMIT_5") (pintype "passive"))
      (node (ref "R24") (pin "1") (pinfunction "1_1") (pintype "passive"))
    )
    (net (code "16") (name "GPA6") (class "Default")
      (node (ref "IC2") (pin "27") (pinfunction "GPA6_27") (pintype "bidirectional"))
      (node (ref "OK4") (pin "7") (pinfunction "EMIT_7") (pintype "passive"))
      (node (ref "R27") (pin "1") (pinfunction "1_1") (pintype "passive"))
    )
    (net (code "17") (name "GPA7") (class "Default")
      (node (ref "IC2") (pin "28") (pinfunction "GPA7_28") (pintype "bidirectional"))
      (node (ref "OK4") (pin "5") (pinfunction "EMIT_5") (pintype "passive"))
      (node (ref "R26") (pin "1") (pinfunction "1_1") (pintype "passive"))
    )
    (net (code "18") (name "GPB0") (class "Default")
      (node (ref "IC2") (pin "1") (pinfunction "GPB0_1") (pintype "bidirectional"))
      (node (ref "R39") (pin "1") (pinfunction "1_1") (pintype "passive"))
    )
    (net (code "19") (name "GPB1") (class "Default")
      (node (ref "IC2") (pin "2") (pinfunction "GPB1_2") (pintype "bidirectional"))
      (node (ref "R34") (pin "1") (pinfunction "1_1") (pintype "passive"))
    )
    (net (code "20") (name "GPB2") (class "Default")
      (node (ref "IC2") (pin "3") (pinfunction "GPB2_3") (pintype "bidirectional"))
      (node (ref "R33") (pin "1") (pinfunction "1_1") (pintype "passive"))
    )
    (net (code "21") (name "GPB3") (class "Default")
      (node (ref "IC2") (pin "4") (pinfunction "GPB3_4") (pintype "bidirectional"))
      (node (ref "R32") (pin "1") (pinfunction "1_1") (pintype "passive"))
    )
    (net (code "22") (name "GPB4") (class "Default")
      (node (ref "IC2") (pin "5") (pinfunction "GPB4_5") (pintype "bidirectional"))
      (node (ref "R31") (pin "1") (pinfunction "1_1") (pintype "passive"))
    )
    (net (code "23") (name "GPB5") (class "Default")
      (node (ref "IC2") (pin "6") (pinfunction "GPB5_6") (pintype "bidirectional"))
      (node (ref "R30") (pin "1") (pinfunction "1_1") (pintype "passive"))
    )
    (net (code "24") (name "GPB6") (class "Default")
      (node (ref "IC2") (pin "7") (pinfunction "GPB6_7") (pintype "bidirectional"))
      (node (ref "OK5") (pin "5") (pinfunction "EMIT_5") (pintype "passive"))
      (node (ref "R38") (pin "1") (pinfunction "1_1") (pintype "passive"))
    )
    (net (code "25") (name "GPB7") (class "Default")
      (node (ref "IC2") (pin "8") (pinfunction "GPB7_8") (pintype "bidirectional"))
      (node (ref "OK5") (pin "7") (pinfunction "EMIT_7") (pintype "passive"))
      (node (ref "R37") (pin "1") (pinfunction "1_1") (pintype "passive"))
    )
    (net (code "26") (name "Net-(BRAKE-Pad1)") (class "Default")
      (node (ref "BRAKE") (pin "1") (pinfunction "1_1") (pintype "passive"))
      (node (ref "D9") (pin "C") (pinfunction "C_C") (pintype "passive"))
      (node (ref "RL1") (pin "P") (pinfunction "P_P") (pintype "passive"))
    )
    (net (code "27") (name "Net-(CN1-PadP$2)") (class "Default")
      (node (ref "CN1") (pin "P$2") (pinfunction "P$2_P$2") (pintype "bidirectional"))
      (node (ref "D1") (pin "A") (pinfunction "A_A") (pintype "passive"))
      (node (ref "D7") (pin "A") (pinfunction "A_A") (pintype "bidirectional"))
      (node (ref "LED3") (pin "C") (pinfunction "C_C") (pintype "passive"))
    )
    (net (code "28") (name "Net-(D2-PadA)") (class "Default")
      (node (ref "D2") (pin "A") (pinfunction "A_A") (pintype "bidirectional"))
      (node (ref "Q2") (pin "C") (pinfunction "C_C") (pintype "passive"))
      (node (ref "RL2") (pin "2") (pinfunction "2_2") (pintype "passive"))
    )
    (net (code "29") (name "Net-(D3-PadA)") (class "Default")
      (node (ref "D3") (pin "A") (pinfunction "A_A") (pintype "bidirectional"))
      (node (ref "Q1") (pin "C") (pinfunction "C_C") (pintype "passive"))
      (node (ref "RL1") (pin "2") (pinfunction "2_2") (pintype "passive"))
    )
    (net (code "30") (name "Net-(D4-PadA)") (class "Default")
      (node (ref "D4") (pin "A") (pinfunction "A_A") (pintype "bidirectional"))
      (node (ref "Q3") (pin "C") (pinfunction "C_C") (pintype "passive"))
      (node (ref "RL3") (pin "2") (pinfunction "2_2") (pintype "passive"))
    )
    (net (code "31") (name "Net-(D6-PadA)") (class "Default")
      (node (ref "D6") (pin "A") (pinfunction "A_A") (pintype "bidirectional"))
      (node (ref "Q4") (pin "C") (pinfunction "C_C") (pintype "passive"))
      (node (ref "RL4") (pin "2") (pinfunction "2_2") (pintype "passive"))
    )
    (net (code "32") (name "Net-(D7-K)") (class "Default")
      (node (ref "D7") (pin "C") (pinfunction "K_C") (pintype "bidirectional"))
      (node (ref "LED3") (pin "A") (pinfunction "A_A") (pintype "passive"))
      (node (ref "R7") (pin "1") (pinfunction "1_1") (pintype "passive"))
    )
    (net (code "33") (name "Net-(D10-PadC)") (class "Default")
      (node (ref "D10") (pin "C") (pinfunction "C_C") (pintype "passive"))
      (node (ref "LOCK") (pin "1") (pinfunction "1_1") (pintype "passive"))
      (node (ref "RL2") (pin "P") (pinfunction "P_P") (pintype "passive"))
    )
    (net (code "34") (name "Net-(D11-PadC)") (class "Default")
      (node (ref "D11") (pin "C") (pinfunction "C_C") (pintype "passive"))
      (node (ref "J3") (pin "1") (pinfunction "1_1") (pintype "passive"))
      (node (ref "RL3") (pin "P") (pinfunction "P_P") (pintype "passive"))
    )
    (net (code "35") (name "Net-(D12-PadC)") (class "Default")
      (node (ref "D12") (pin "C") (pinfunction "C_C") (pintype "passive"))
      (node (ref "J4") (pin "1") (pinfunction "1_1") (pintype "passive"))
      (node (ref "RL4") (pin "P") (pinfunction "P_P") (pintype "passive"))
    )
    (net (code "36") (name "Net-(IC1-OUT)") (class "Default")
      (node (ref "D5") (pin "C") (pinfunction "C_C") (pintype "passive"))
      (node (ref "IC1") (pin "2") (pinfunction "OUT_2") (pintype "output"))
      (node (ref "L1") (pin "1") (pinfunction "1_1") (pintype "passive"))
    )
    (net (code "37") (name "Net-(J1-Pad1)") (class "Default")
      (node (ref "J1") (pin "1") (pinfunction "1_1") (pintype "passive"))
      (node (ref "R18") (pin "2") (pinfunction "2_2") (pintype "passive"))
    )
    (net (code "38") (name "Net-(J1-Pad2)") (class "Default")
      (node (ref "J1") (pin "2") (pinfunction "2_2") (pintype "passive"))
      (node (ref "R19") (pin "2") (pinfunction "2_2") (pintype "passive"))
    )
    (net (code "39") (name "Net-(J1-Pad3)") (class "Default")
      (node (ref "J1") (pin "3") (pinfunction "3_3") (pintype "passive"))
      (node (ref "R16") (pin "2") (pinfunction "2_2") (pintype "passive"))
    )
    (net (code "40") (name "Net-(J1-Pad4)") (class "Default")
      (node (ref "J1") (pin "4") (pinfunction "4_4") (pintype "passive"))
      (node (ref "R17") (pin "2") (pinfunction "2_2") (pintype "passive"))
    )
    (net (code "41") (name "Net-(J1-Pad5)") (class "Default")
      (node (ref "J1") (pin "5") (pinfunction "5_5") (pintype "passive"))
      (node (ref "R14") (pin "2") (pinfunction "2_2") (pintype "passive"))
    )
    (net (code "42") (name "Net-(J1-Pad6)") (class "Default")
      (node (ref "J1") (pin "6") (pinfunction "6_6") (pintype "passive"))
      (node (ref "R15") (pin "2") (pinfunction "2_2") (pintype "passive"))
    )
    (net (code "43") (name "Net-(J2-Pad2)") (class "Default")
      (node (ref "J2") (pin "2") (pinfunction "2_2") (pintype "passive"))
      (node (ref "R28") (pin "1") (pinfunction "1_1") (pintype "passive"))
    )
    (net (code "44") (name "Net-(J5-Pad2)") (class "Default")
      (node (ref "J5") (pin "2") (pinfunction "2_2") (pintype "passive"))
      (node (ref "R29") (pin "1") (pinfunction "1_1") (pintype "passive"))
    )
    (net (code "45") (name "Net-(J9-Pad1)") (class "Default")
      (node (ref "J9") (pin "1") (pinfunction "1_1") (pintype "passive"))
      (node (ref "R35") (pin "2") (pinfunction "2_2") (pintype "passive"))
    )
    (net (code "46") (name "Net-(J10-Pad1)") (class "Default")
      (node (ref "J10") (pin "1") (pinfunction "1_1") (pintype "passive"))
      (node (ref "R36") (pin "2") (pinfunction "2_2") (pintype "passive"))
    )
    (net (code "47") (name "Net-(LED1-PadA)") (class "Default")
      (node (ref "LED1") (pin "A") (pinfunction "A_A") (pintype "passive"))
      (node (ref "R5") (pin "1") (pinfunction "1_1") (pintype "passive"))
    )
    (net (code "48") (name "Net-(LED2-PadA)") (class "Default")
      (node (ref "LED2") (pin "A") (pinfunction "A_A") (pintype "passive"))
      (node (ref "R6") (pin "1") (pinfunction "1_1") (pintype "passive"))
    )
    (net (code "49") (name "Net-(LED4-PadA)") (class "Default")
      (node (ref "LED4") (pin "A") (pinfunction "A_A") (pintype "passive"))
      (node (ref "R11") (pin "2") (pinfunction "2_2") (pintype "passive"))
    )
    (net (code "50") (name "Net-(LED5-PadA)") (class "Default")
      (node (ref "LED5") (pin "A") (pinfunction "A_A") (pintype "passive"))
      (node (ref "R10") (pin "2") (pinfunction "2_2") (pintype "passive"))
    )
    (net (code "51") (name "Net-(LED6-PadA)") (class "Default")
      (node (ref "LED6") (pin "A") (pinfunction "A_A") (pintype "passive"))
      (node (ref "R9") (pin "2") (pinfunction "2_2") (pintype "passive"))
    )
    (net (code "52") (name "Net-(LED7-PadA)") (class "Default")
      (node (ref "LED7") (pin "A") (pinfunction "A_A") (pintype "passive"))
      (node (ref "R8") (pin "2") (pinfunction "2_2") (pintype "passive"))
    )
    (net (code "53") (name "Net-(OK1A-A)") (class "Default")
      (node (ref "OK1") (pin "1") (pinfunction "A_1") (pintype "passive"))
      (node (ref "R14") (pin "1") (pinfunction "1_1") (pintype "passive"))
    )
    (net (code "54") (name "Net-(OK1B-A)") (class "Default")
      (node (ref "OK1") (pin "3") (pinfunction "A_3") (pintype "passive"))
      (node (ref "R15") (pin "1") (pinfunction "1_1") (pintype "passive"))
    )
    (net (code "55") (name "Net-(OK2A-A)") (class "Default")
      (node (ref "OK2") (pin "1") (pinfunction "A_1") (pintype "passive"))
      (node (ref "R16") (pin "1") (pinfunction "1_1") (pintype "passive"))
    )
    (net (code "56") (name "Net-(OK2B-A)") (class "Default")
      (node (ref "OK2") (pin "3") (pinfunction "A_3") (pintype "passive"))
      (node (ref "R17") (pin "1") (pinfunction "1_1") (pintype "passive"))
    )
    (net (code "57") (name "Net-(OK3A-A)") (class "Default")
      (node (ref "OK3") (pin "1") (pinfunction "A_1") (pintype "passive"))
      (node (ref "R18") (pin "1") (pinfunction "1_1") (pintype "passive"))
    )
    (net (code "58") (name "Net-(OK3B-A)") (class "Default")
      (node (ref "OK3") (pin "3") (pinfunction "A_3") (pintype "passive"))
      (node (ref "R19") (pin "1") (pinfunction "1_1") (pintype "passive"))
    )
    (net (code "59") (name "Net-(OK4A-A)") (class "Default")
      (node (ref "OK4") (pin "1") (pinfunction "A_1") (pintype "passive"))
      (node (ref "R28") (pin "2") (pinfunction "2_2") (pintype "passive"))
    )
    (net (code "60") (name "Net-(OK4B-A)") (class "Default")
      (node (ref "OK4") (pin "3") (pinfunction "A_3") (pintype "passive"))
      (node (ref "R29") (pin "2") (pinfunction "2_2") (pintype "passive"))
    )
    (net (code "61") (name "Net-(OK5A-A)") (class "Default")
      (node (ref "OK5") (pin "1") (pinfunction "A_1") (pintype "passive"))
      (node (ref "R35") (pin "1") (pinfunction "1_1") (pintype "passive"))
    )
    (net (code "62") (name "Net-(OK5B-A)") (class "Default")
      (node (ref "OK5") (pin "3") (pinfunction "A_3") (pintype "passive"))
      (node (ref "R36") (pin "1") (pinfunction "1_1") (pintype "passive"))
    )
    (net (code "63") (name "Net-(Q1-PadB)") (class "Default")
      (node (ref "Q1") (pin "B") (pinfunction "B_B") (pintype "passive"))
      (node (ref "R1") (pin "2") (pinfunction "2_2") (pintype "passive"))
    )
    (net (code "64") (name "Net-(Q2-PadB)") (class "Default")
      (node (ref "Q2") (pin "B") (pinfunction "B_B") (pintype "passive"))
      (node (ref "R2") (pin "2") (pinfunction "2_2") (pintype "passive"))
    )
    (net (code "65") (name "Net-(Q3-PadB)") (class "Default")
      (node (ref "Q3") (pin "B") (pinfunction "B_B") (pintype "passive"))
      (node (ref "R3") (pin "2") (pinfunction "2_2") (pintype "passive"))
    )
    (net (code "66") (name "Net-(Q4-PadB)") (class "Default")
      (node (ref "Q4") (pin "B") (pinfunction "B_B") (pintype "passive"))
      (node (ref "R4") (pin "2") (pinfunction "2_2") (pintype "passive"))
    )
    (net (code "67") (name "RL1") (class "Default")
      (node (ref "R1") (pin "1") (pinfunction "1_1") (pintype "passive"))
      (node (ref "R8") (pin "1") (pinfunction "1_1") (pintype "passive"))
      (node (ref "U$1") (pin "A0") (pinfunction "A0_A0") (pintype "bidirectional"))
    )
    (net (code "68") (name "RL2") (class "Default")
      (node (ref "R2") (pin "1") (pinfunction "1_1") (pintype "passive"))
      (node (ref "R9") (pin "1") (pinfunction "1_1") (pintype "passive"))
      (node (ref "U$1") (pin "A1") (pinfunction "A1_A1") (pintype "bidirectional"))
    )
    (net (code "69") (name "RL3") (class "Default")
      (node (ref "R10") (pin "1") (pinfunction "1_1") (pintype "passive"))
      (node (ref "R3") (pin "1") (pinfunction "1_1") (pintype "passive"))
      (node (ref "U$1") (pin "A2") (pinfunction "A2_A2") (pintype "bidirectional"))
    )
    (net (code "70") (name "RL4") (class "Default")
      (node (ref "R11") (pin "1") (pinfunction "1_1") (pintype "passive"))
      (node (ref "R4") (pin "1") (pinfunction "1_1") (pintype "passive"))
      (node (ref "U$1") (pin "A3") (pinfunction "A3_A3") (pintype "bidirectional"))
    )
    (net (code "71") (name "SCL") (class "Default")
      (node (ref "IC2") (pin "12") (pinfunction "SCL_12") (pintype "input"))
      (node (ref "R13") (pin "1") (pinfunction "1_1") (pintype "passive"))
      (node (ref "U$1") (pin "A5") (pinfunction "A5_A5") (pintype "bidirectional"))
    )
    (net (code "72") (name "SDA") (class "Default")
      (node (ref "IC2") (pin "13") (pinfunction "SDA_13") (pintype "bidirectional"))
      (node (ref "R12") (pin "1") (pinfunction "1_1") (pintype "passive"))
      (node (ref "U$1") (pin "A4") (pinfunction "A4_A4") (pintype "bidirectional"))
    )
    (net (code "73") (name "STEP") (class "Default")
      (node (ref "J6") (pin "1") (pinfunction "1_1") (pintype "passive"))
      (node (ref "U$1") (pin "D11") (pinfunction "D11_D11") (pintype "bidirectional"))
    )
    (net (code "74") (name "VCC") (class "Default")
      (node (ref "C3") (pin "+") (pinfunction "+_+") (pintype "passive"))
      (node (ref "D1") (pin "C") (pinfunction "C_C") (pintype "passive"))
      (node (ref "D2") (pin "C") (pinfunction "K_C") (pintype "bidirectional"))
      (node (ref "D3") (pin "C") (pinfunction "K_C") (pintype "bidirectional"))
      (node (ref "D4") (pin "C") (pinfunction "K_C") (pintype "bidirectional"))
      (node (ref "D6") (pin "C") (pinfunction "K_C") (pintype "bidirectional"))
      (node (ref "IC1") (pin "1") (pinfunction "VIN_1") (pintype "input"))
      (node (ref "J1") (pin "8") (pinfunction "8_8") (pintype "passive"))
      (node (ref "J10") (pin "2") (pinfunction "2_2") (pintype "passive"))
      (node (ref "J2") (pin "3") (pinfunction "3_3") (pintype "passive"))
      (node (ref "J5") (pin "3") (pinfunction "3_3") (pintype "passive"))
      (node (ref "J9") (pin "2") (pinfunction "2_2") (pintype "passive"))
      (node (ref "R5") (pin "2") (pinfunction "2_2") (pintype "passive"))
      (node (ref "RL1") (pin "1") (pinfunction "1_1") (pintype "passive"))
      (node (ref "RL1") (pin "S") (pinfunction "S_S") (pintype "passive"))
      (node (ref "RL2") (pin "1") (pinfunction "1_1") (pintype "passive"))
      (node (ref "RL2") (pin "S") (pinfunction "S_S") (pintype "passive"))
      (node (ref "RL3") (pin "1") (pinfunction "1_1") (pintype "passive"))
      (node (ref "RL3") (pin "S") (pinfunction "S_S") (pintype "passive"))
      (node (ref "RL4") (pin "1") (pinfunction "1_1") (pintype "passive"))
      (node (ref "RL4") (pin "S") (pinfunction "S_S") (pintype "passive"))
    )
    (net (code "75") (name "unconnected-(IC2-INTA-Pad20)") (class "Default")
      (node (ref "IC2") (pin "20") (pinfunction "INTA_20") (pintype "output"))
    )
    (net (code "76") (name "unconnected-(IC2-INTB-Pad19)") (class "Default")
      (node (ref "IC2") (pin "19") (pinfunction "INTB_19") (pintype "output"))
    )
    (net (code "77") (name "unconnected-(RL1-PadO)") (class "Default")
      (node (ref "RL1") (pin "O") (pinfunction "O_O") (pintype "passive"))
    )
    (net (code "78") (name "unconnected-(RL2-PadO)") (class "Default")
      (node (ref "RL2") (pin "O") (pinfunction "O_O") (pintype "passive"))
    )
    (net (code "79") (name "unconnected-(RL3-PadO)") (class "Default")
      (node (ref "RL3") (pin "O") (pinfunction "O_O") (pintype "passive"))
    )
    (net (code "80") (name "unconnected-(RL4-PadO)") (class "Default")
      (node (ref "RL4") (pin "O") (pinfunction "O_O") (pintype "passive"))
    )
    (net (code "81") (name "unconnected-(U$1-Pad3.3V)") (class "Default")
      (node (ref "U$1") (pin "3.3V") (pinfunction "3.3V_3.3V") (pintype "bidirectional"))
    )
    (net (code "82") (name "unconnected-(U$1-PadA6)") (class "Default")
      (node (ref "U$1") (pin "A6") (pinfunction "A6_A6") (pintype "bidirectional"))
    )
    (net (code "83") (name "unconnected-(U$1-PadA7)") (class "Default")
      (node (ref "U$1") (pin "A7") (pinfunction "A7_A7") (pintype "bidirectional"))
    )
    (net (code "84") (name "unconnected-(U$1-PadAREF)") (class "Default")
      (node (ref "U$1") (pin "AREF") (pinfunction "AREF_AREF") (pintype "bidirectional"))
    )
    (net (code "85") (name "unconnected-(U$1-PadD2)") (class "Default")
      (node (ref "U$1") (pin "D2") (pinfunction "D2_D2") (pintype "bidirectional"))
    )
    (net (code "86") (name "unconnected-(U$1-PadD3)") (class "Default")
      (node (ref "U$1") (pin "D3") (pinfunction "D3_D3") (pintype "bidirectional"))
    )
    (net (code "87") (name "unconnected-(U$1-PadD4)") (class "Default")
      (node (ref "U$1") (pin "D4") (pinfunction "D4_D4") (pintype "bidirectional"))
    )
    (net (code "88") (name "unconnected-(U$1-PadD5)") (class "Default")
      (node (ref "U$1") (pin "D5") (pinfunction "D5_D5") (pintype "bidirectional"))
    )
    (net (code "89") (name "unconnected-(U$1-PadD6)") (class "Default")
      (node (ref "U$1") (pin "D6") (pinfunction "D6_D6") (pintype "bidirectional"))
    )
    (net (code "90") (name "unconnected-(U$1-PadD7)") (class "Default")
      (node (ref "U$1") (pin "D7") (pinfunction "D7_D7") (pintype "bidirectional"))
    )
    (net (code "91") (name "unconnected-(U$1-PadD8)") (class "Default")
      (node (ref "U$1") (pin "D8") (pinfunction "D8_D8") (pintype "bidirectional"))
    )
    (net (code "92") (name "unconnected-(U$1-PadD9)") (class "Default")
      (node (ref "U$1") (pin "D9") (pinfunction "D9_D9") (pintype "bidirectional"))
    )
    (net (code "93") (name "unconnected-(U$1-PadD10)") (class "Default")
      (node (ref "U$1") (pin "D10") (pinfunction "D10_D10") (pintype "bidirectional"))
    )
    (net (code "94") (name "unconnected-(U$1-PadD13)") (class "Default")
      (node (ref "U$1") (pin "D13") (pinfunction "D13_D13") (pintype "bidirectional"))
    )
    (net (code "95") (name "unconnected-(U$1-PadRAW)") (class "Default")
      (node (ref "U$1") (pin "RAW") (pinfunction "RAW_RAW") (pintype "bidirectional"))
    )
    (net (code "96") (name "unconnected-(U$1-PadRST)") (class "Default")
      (node (ref "U$1") (pin "RST") (pinfunction "RST_RST") (pintype "bidirectional"))
    )
    (net (code "97") (name "unconnected-(U$1-PadRST1)") (class "Default")
      (node (ref "U$1") (pin "RST1") (pinfunction "RST1_RST1") (pintype "bidirectional"))
    )
    (net (code "98") (name "unconnected-(U$1-PadRX1)") (class "Default")
      (node (ref "U$1") (pin "RX1") (pinfunction "RX1_RX1") (pintype "bidirectional"))
    )
    (net (code "99") (name "unconnected-(U$1-PadTX0)") (class "Default")
      (node (ref "U$1") (pin "TX0") (pinfunction "TX0_TX0") (pintype "bidirectional"))
    )
  )
)
